# 04_Misc_IO.net
KiCad netlist of a schematic drawn in Altium Designer
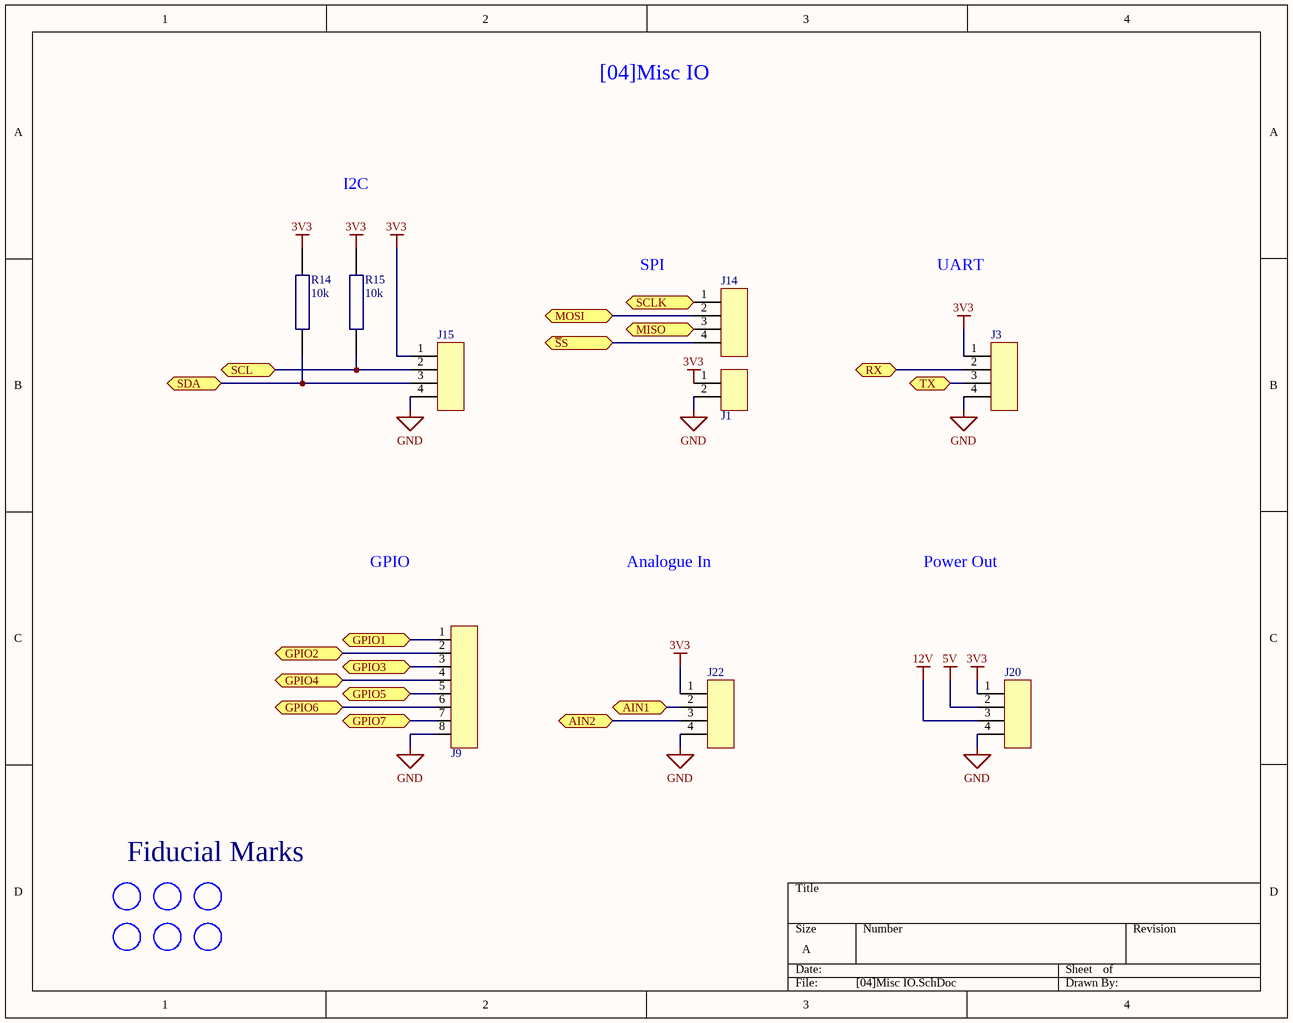
[diagram p0: [04]Misc IO.SchDoc]

(export (version "E")
  (design (tool "Eeschema 10.0.6"))
  (components
    (comp (ref "FID1")
      (value "FID?")
      (footprint "fiducial")
      (libsource (lib "AMMDK Parts") (part "fiducial"))
    )
    (comp (ref "FID2")
      (value "FID?")
      (footprint "fiducial")
      (libsource (lib "AMMDK Parts") (part "fiducial"))
    )
    (comp (ref "FID3")
      (value "FID?")
      (footprint "fiducial")
      (libsource (lib "AMMDK Parts") (part "fiducial"))
    )
    (comp (ref "FID4")
      (value "FID?")
      (footprint "fiducial")
      (libsource (lib "AMMDK Parts") (part "fiducial"))
    )
    (comp (ref "FID5")
      (value "FID?")
      (footprint "fiducial")
      (libsource (lib "AMMDK Parts") (part "fiducial"))
    )
    (comp (ref "FID6")
      (value "FID?")
      (footprint "fiducial")
      (libsource (lib "AMMDK Parts") (part "fiducial"))
    )
    (comp (ref "J1")
      (value "282834-2")
      (footprint "282834-2")
      (description "2 Position Wire to Board Terminal Block")
      (libsource (lib "AMMDK Parts") (part "282834-2"))
    )
    (comp (ref "J3")
      (value "282834-4")
      (footprint "282834-4")
      (description "4 Position Wire to Board Terminal Block")
      (libsource (lib "AMMDK Parts") (part "282834-4"))
    )
    (comp (ref "J9")
      (value "1771156")
      (footprint "1771156")
      (description "CONN TERM BLK 8POS 2.5MM SMD")
      (fields (field (name "MANUFACTURER") "Phoenix Contact"))
      (libsource (lib "AMMDK Parts") (part "1771156"))
    )
    (comp (ref "J14")
      (value "282834-4")
      (footprint "282834-4")
      (description "4 Position Wire to Board Terminal Block")
      (libsource (lib "AMMDK Parts") (part "282834-4"))
    )
    (comp (ref "J15")
      (value "282834-4")
      (footprint "282834-4")
      (description "4 Position Wire to Board Terminal Block")
      (libsource (lib "AMMDK Parts") (part "282834-4"))
    )
    (comp (ref "J20")
      (value "282834-4")
      (footprint "282834-4")
      (description "4 Position Wire to Board Terminal Block")
      (libsource (lib "AMMDK Parts") (part "282834-4"))
    )
    (comp (ref "J22")
      (value "282834-4")
      (footprint "282834-4")
      (description "4 Position Wire to Board Terminal Block")
      (libsource (lib "AMMDK Parts") (part "282834-4"))
    )
    (comp (ref "R14")
      (value "10k")
      (footprint "RESC2012X07N_SAMSUNG")
      (description "RES SMD 10K OHM 1% 1/8W 0805")
      (fields
        (field (name "MANUFACTURER") "Samsung Electro-Mechanics America, Inc.")
        (field (name "MANUFACTURER PART NUMBER") "RC2012F103CS")
      )
      (libsource (lib "AMMDK Parts") (part "RC2012F103CS"))
    )
    (comp (ref "R15")
      (value "10k")
      (footprint "RESC2012X07N_SAMSUNG")
      (description "RES SMD 10K OHM 1% 1/8W 0805")
      (fields
        (field (name "MANUFACTURER") "Samsung Electro-Mechanics America, Inc.")
        (field (name "MANUFACTURER PART NUMBER") "RC2012F103CS")
      )
      (libsource (lib "AMMDK Parts") (part "RC2012F103CS"))
    )
  )
  (nets
    (net (code "1") (name "/AIN1") (class "Default") (node (ref "J22") (pin "2") (pintype "passive")))
    (net (code "2") (name "/AIN2") (class "Default") (node (ref "J22") (pin "3") (pintype "passive")))
    (net (code "3") (name "/GPIO1") (class "Default")
      (node (ref "J9") (pin "1") (pinfunction "1_1") (pintype "passive"))
    )
    (net (code "4") (name "/GPIO2") (class "Default")
      (node (ref "J9") (pin "2") (pinfunction "2_2") (pintype "passive"))
    )
    (net (code "5") (name "/GPIO3") (class "Default")
      (node (ref "J9") (pin "3") (pinfunction "3_3") (pintype "passive"))
    )
    (net (code "6") (name "/GPIO4") (class "Default")
      (node (ref "J9") (pin "4") (pinfunction "4_4") (pintype "passive"))
    )
    (net (code "7") (name "/GPIO5") (class "Default")
      (node (ref "J9") (pin "5") (pinfunction "5_5") (pintype "passive"))
    )
    (net (code "8") (name "/GPIO6") (class "Default")
      (node (ref "J9") (pin "6") (pinfunction "6_6") (pintype "passive"))
    )
    (net (code "9") (name "/GPIO7") (class "Default")
      (node (ref "J9") (pin "7") (pinfunction "7_7") (pintype "passive"))
    )
    (net (code "10") (name "/MISO") (class "Default") (node (ref "J14") (pin "3") (pintype "passive")))
    (net (code "11") (name "/MOSI") (class "Default") (node (ref "J14") (pin "2") (pintype "passive")))
    (net (code "12") (name "/RX") (class "Default") (node (ref "J3") (pin "2") (pintype "passive")))
    (net (code "13") (name "/SCL") (class "Default")
      (node (ref "J15") (pin "2") (pintype "passive"))
      (node (ref "R15") (pin "1") (pinfunction "1_1") (pintype "passive"))
    )
    (net (code "14") (name "/SCLK") (class "Default") (node (ref "J14") (pin "1") (pintype "passive")))
    (net (code "15") (name "/SDA") (class "Default")
      (node (ref "J15") (pin "3") (pintype "passive"))
      (node (ref "R14") (pin "1") (pinfunction "1_1") (pintype "passive"))
    )
    (net (code "16") (name "/TX") (class "Default") (node (ref "J3") (pin "3") (pintype "passive")))
    (net (code "17") (name "/~{S}S") (class "Default") (node (ref "J14") (pin "4") (pintype "passive")))
    (net (code "18") (name "3V3") (class "Default")
      (node (ref "J1") (pin "1") (pintype "passive"))
      (node (ref "J15") (pin "1") (pintype "passive"))
      (node (ref "J20") (pin "1") (pintype "passive"))
      (node (ref "J22") (pin "1") (pintype "passive"))
      (node (ref "J3") (pin "1") (pintype "passive"))
      (node (ref "R14") (pin "2") (pinfunction "2_2") (pintype "passive"))
      (node (ref "R15") (pin "2") (pinfunction "2_2") (pintype "passive"))
    )
    (net (code "19") (name "5V") (class "Default") (node (ref "J20") (pin "2") (pintype "passive")))
    (net (code "20") (name "12V") (class "Default") (node (ref "J20") (pin "3") (pintype "passive")))
    (net (code "21") (name "GND") (class "Default")
      (node (ref "J1") (pin "2") (pintype "passive"))
      (node (ref "J15") (pin "4") (pintype "passive"))
      (node (ref "J20") (pin "4") (pintype "passive"))
      (node (ref "J22") (pin "4") (pintype "passive"))
      (node (ref "J3") (pin "4") (pintype "passive"))
      (node (ref "J9") (pin "8") (pinfunction "8_8") (pintype "passive"))
    )
  )
)
